# 1-Schematic_ISM_WAVER.net
KiCad netlist of a schematic drawn in EasyEDA
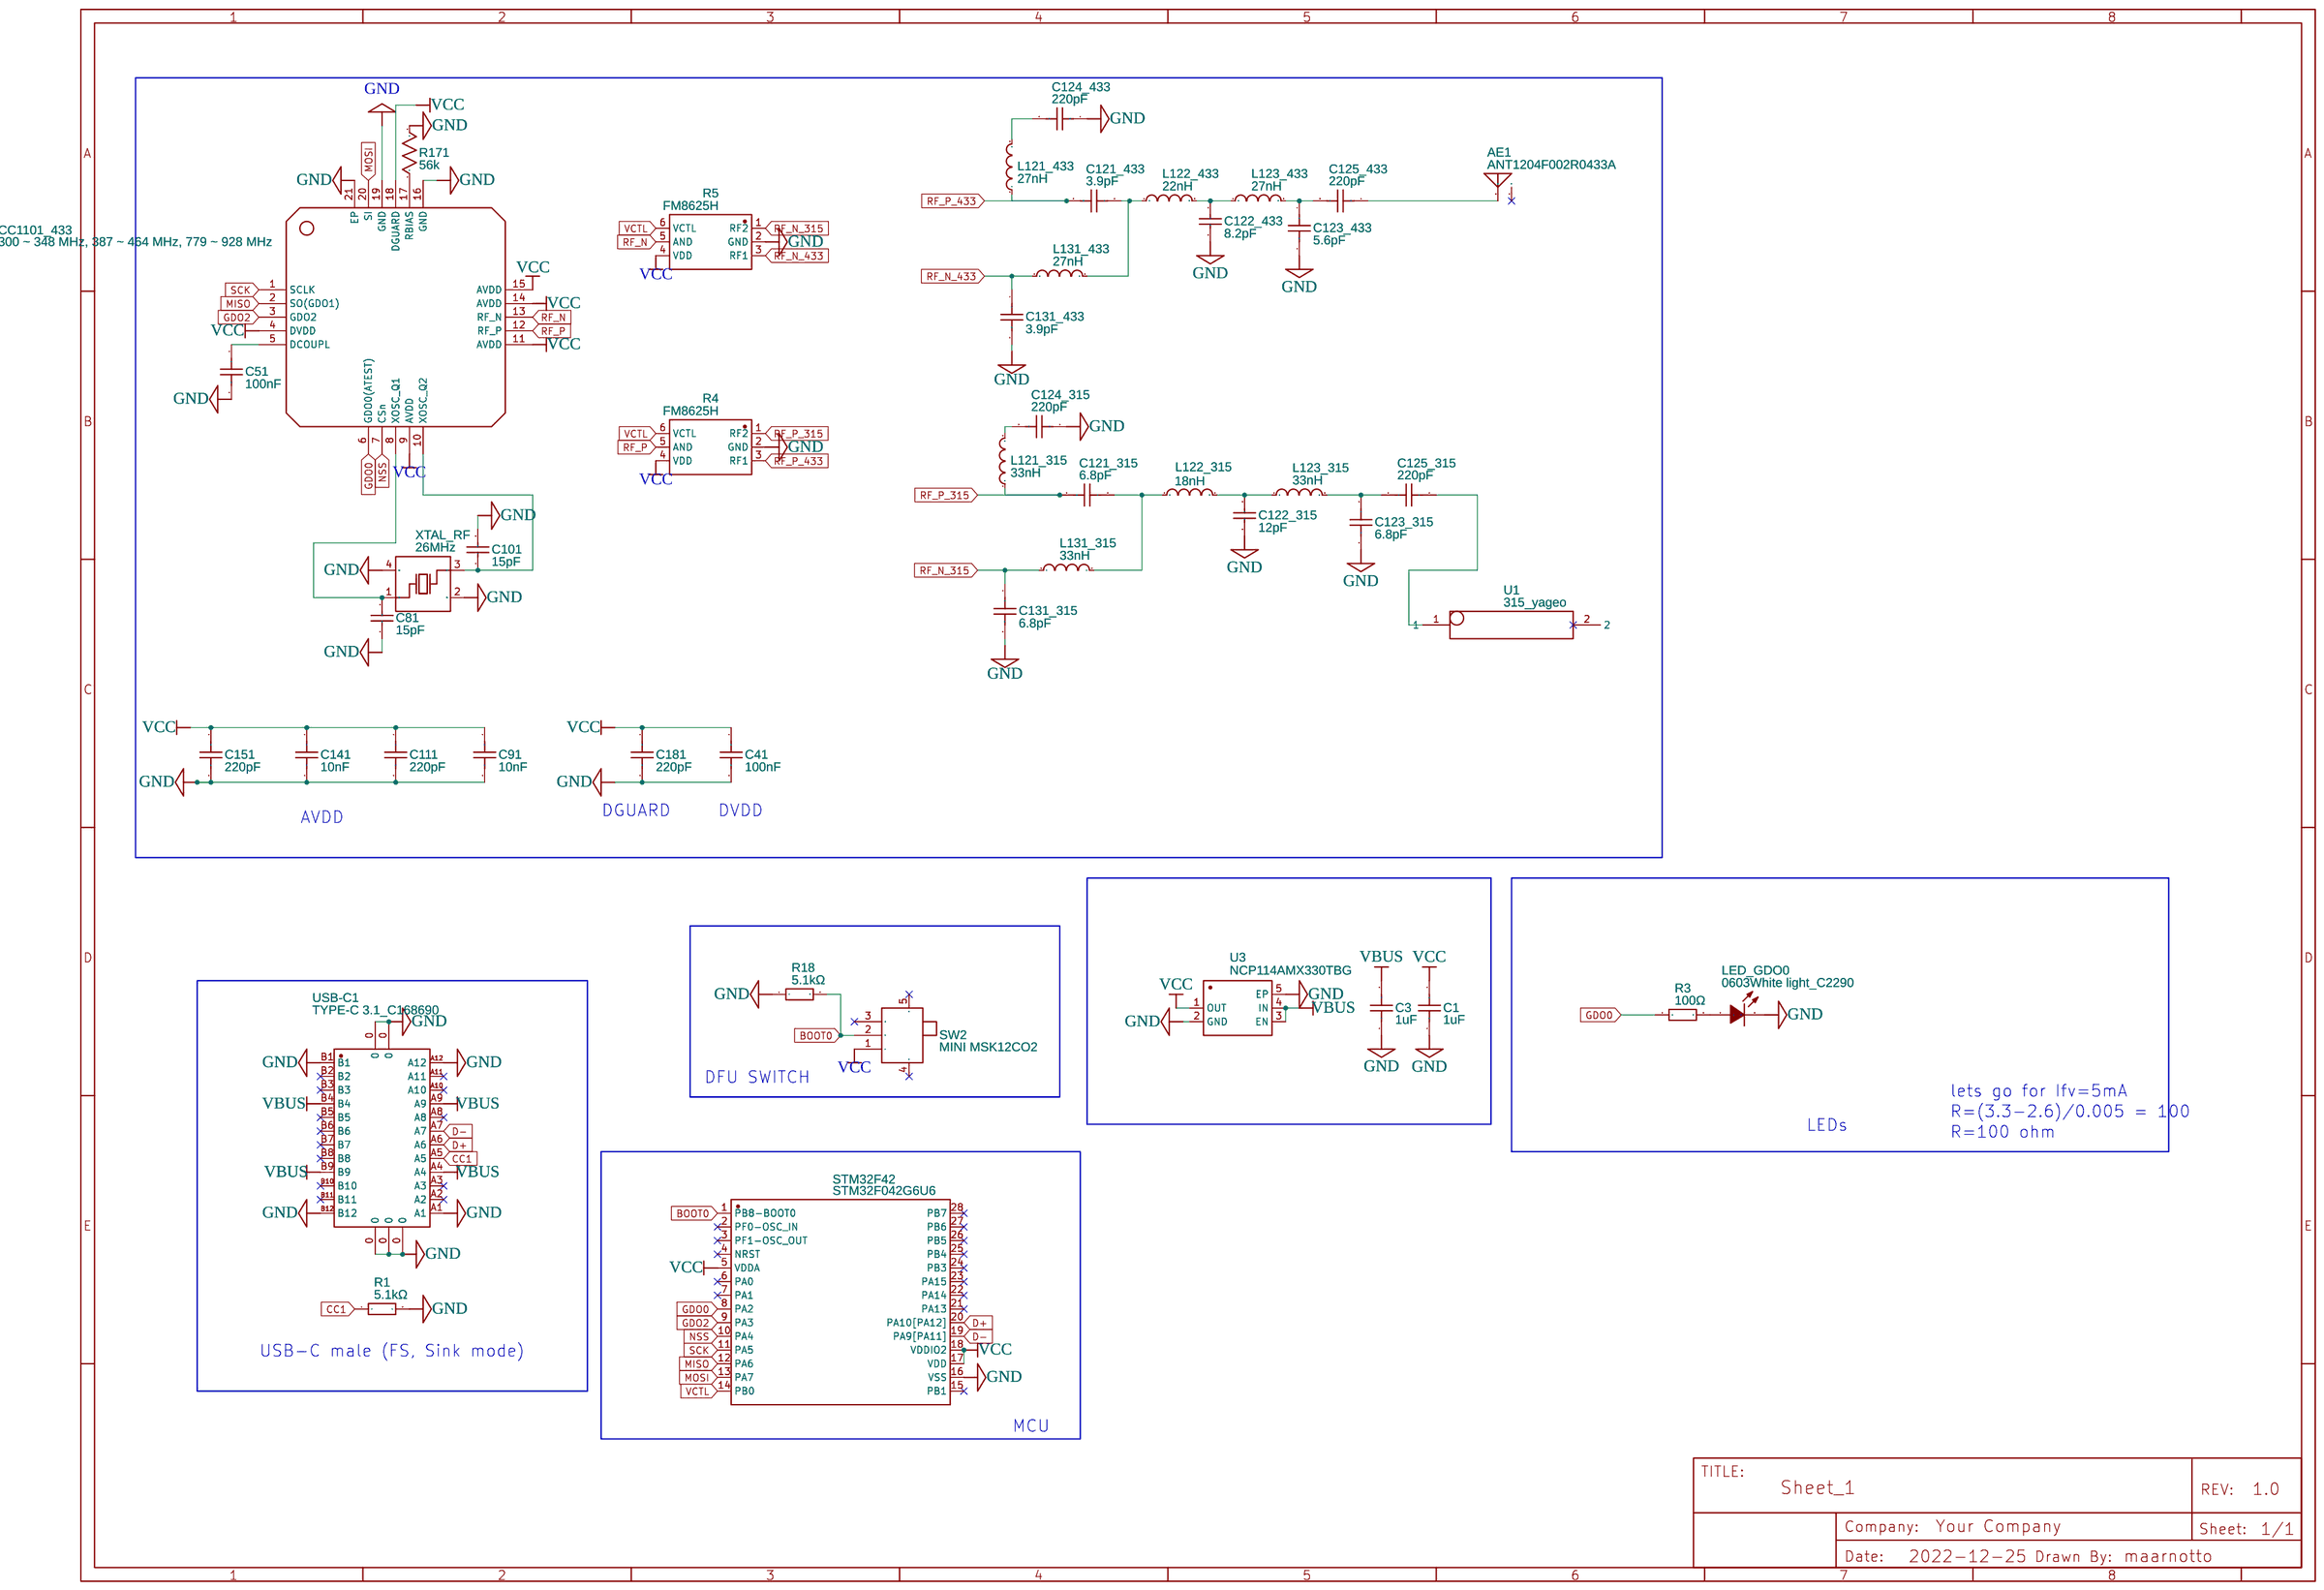
[diagram p0: schematic sheet]

(export (version "E")
  (design (tool "Eeschema 10.0.6"))
  (components
    (comp (ref "AE1")
      (value "ANT1204F002R0433A")
      (fields (field (name "Manufacturer") "YAGEO(国巨)"))
      (libsource (lib "") (part "ANT1204F002R0433A"))
    )
    (comp (ref "C1") (value "1uF") (libsource (lib "") (part "C_0603_US")))
    (comp (ref "C3") (value "1uF") (libsource (lib "") (part "C_0603_US")))
    (comp (ref "C41") (value "100nF") (libsource (lib "") (part "C_0402_US_1")))
    (comp (ref "C51") (value "100nF") (libsource (lib "") (part "C_0402_US_1")))
    (comp (ref "C81")
      (value "15pF")
      (fields (field (name "Manufacturer Part") "0402CG150J500NT") (field (name "Manufacturer") "FH(风华)"))
      (libsource (lib "") (part "0402CG150J500NT"))
    )
    (comp (ref "C91") (value "10nF") (libsource (lib "") (part "C_0402_US_1")))
    (comp (ref "C101")
      (value "15pF")
      (fields (field (name "Manufacturer Part") "0402CG150J500NT") (field (name "Manufacturer") "FH(风华)"))
      (libsource (lib "") (part "0402CG150J500NT"))
    )
    (comp (ref "C111") (value "220pF") (libsource (lib "") (part "C_0402_US_1")))
    (comp (ref "C121_315") (value "6.8pF") (libsource (lib "") (part "C_0402_US_2")))
    (comp (ref "C121_433") (value "3.9pF") (libsource (lib "") (part "C_0402_US_2")))
    (comp (ref "C122_315")
      (value "12pF")
      (fields (field (name "Manufacturer Part") "0402CG8R2C500NT") (field (name "Manufacturer") "FH(风华)"))
      (libsource (lib "") (part "0402CG8R2C500NT"))
    )
    (comp (ref "C122_433")
      (value "8.2pF")
      (fields (field (name "Manufacturer Part") "0402CG8R2C500NT") (field (name "Manufacturer") "FH(风华)"))
      (libsource (lib "") (part "0402CG8R2C500NT"))
    )
    (comp (ref "C123_315") (value "6.8pF") (libsource (lib "") (part "C_0402_US_3")))
    (comp (ref "C123_433") (value "5.6pF") (libsource (lib "") (part "C_0402_US_3")))
    (comp (ref "C124_315") (value "220pF") (libsource (lib "") (part "C_0402_US")))
    (comp (ref "C124_433") (value "220pF") (libsource (lib "") (part "C_0402_US")))
    (comp (ref "C125_315") (value "220pF") (libsource (lib "") (part "C_0402_US_4")))
    (comp (ref "C125_433") (value "220pF") (libsource (lib "") (part "C_0402_US_4")))
    (comp (ref "C131_315") (value "6.8pF") (libsource (lib "") (part "C_0402_US_5")))
    (comp (ref "C131_433") (value "3.9pF") (libsource (lib "") (part "C_0402_US_5")))
    (comp (ref "C141") (value "10nF") (libsource (lib "") (part "C_0402_US_1")))
    (comp (ref "C151") (value "220pF") (libsource (lib "") (part "C_0402_US_1")))
    (comp (ref "C181") (value "220pF") (libsource (lib "") (part "C_0402_US_1")))
    (comp (ref "CC1101_433")
      (value "300 ~ 348 MHz, 387 ~ 464 MHz, 779 ~ 928 MHz")
      (fields (field (name "Manufacturer Part") "CC1101RGPR") (field (name "Manufacturer") "TI(德州仪器)"))
      (libsource (lib "") (part "CC1101RGPR"))
    )
    (comp (ref "L121_315") (value "33nH") (libsource (lib "") (part "L0402_US")))
    (comp (ref "L121_433") (value "27nH") (libsource (lib "") (part "L0402_US")))
    (comp (ref "L122_315") (value "18nH") (libsource (lib "") (part "L0402_US_3")))
    (comp (ref "L122_433") (value "22nH") (libsource (lib "") (part "L0402_US_3")))
    (comp (ref "L123_315") (value "33nH") (libsource (lib "") (part "L0402_US_1")))
    (comp (ref "L123_433") (value "27nH") (libsource (lib "") (part "L0402_US_1")))
    (comp (ref "L131_315") (value "33nH") (libsource (lib "") (part "L0402_US_2")))
    (comp (ref "L131_433") (value "27nH") (libsource (lib "") (part "L0402_US_2")))
    (comp (ref "LED_GDO0")
      (value "0603White light_C2290")
      (fields (field (name "Manufacturer Part") "KT-0603白灯") (field (name "Manufacturer") "KENTO"))
      (libsource (lib "") (part "0603White light_C2290"))
    )
    (comp (ref "R1")
      (value "5.1kΩ")
      (fields
        (field (name "Manufacturer Part") "0402WGF5101TCE")
        (field (name "Manufacturer") "UNI-ROYAL(厚声)")
      )
      (libsource (lib "") (part "0402WGF5101TCE"))
    )
    (comp (ref "R3")
      (value "100Ω")
      (fields
        (field (name "Manufacturer Part") "0603WAF1000T5E")
        (field (name "Manufacturer") "UNI-ROYAL(厚声)")
      )
      (libsource (lib "") (part "0603WAF1000T5E"))
    )
    (comp (ref "R4")
      (value "FM8625H")
      (fields (field (name "Manufacturer") "FM(富满)"))
      (libsource (lib "") (part "FM8625H"))
    )
    (comp (ref "R5")
      (value "FM8625H")
      (fields (field (name "Manufacturer") "FM(富满)"))
      (libsource (lib "") (part "FM8625H"))
    )
    (comp (ref "R18")
      (value "5.1kΩ")
      (fields
        (field (name "Manufacturer Part") "0402WGF5101TCE")
        (field (name "Manufacturer") "UNI-ROYAL(厚声)")
      )
      (libsource (lib "") (part "0402WGF5101TCE"))
    )
    (comp (ref "R171") (value "56k") (libsource (lib "") (part "R_0402_US")))
    (comp (ref "STM32F42")
      (value "STM32F042G6U6")
      (fields (field (name "Manufacturer") "ST(意法半导体)"))
      (libsource (lib "") (part "STM32F042G6U6"))
    )
    (comp (ref "SW2")
      (value "MINI MSK12CO2")
      (fields (field (name "Manufacturer") "SHOU HAN(首韩)"))
      (libsource (lib "") (part "MINI MSK12CO2"))
    )
    (comp (ref "U1")
      (value "315_yageo")
      (fields
        (field (name "Manufacturer Part") "ANT1204F002R0315A")
        (field (name "Manufacturer") "PULSE ELECTRONICS")
      )
      (libsource (lib "") (part "315_yageo"))
    )
    (comp (ref "U3")
      (value "NCP114AMX330TBG")
      (fields (field (name "Manufacturer") "onsemi(安森美)"))
      (libsource (lib "") (part "NCP114AMX330TBG"))
    )
    (comp (ref "USB-C1")
      (value "TYPE-C 3.1_C168690")
      (fields (field (name "Manufacturer Part") "918-118A2021Y40000") (field (name "Manufacturer") "精拓金"))
      (libsource (lib "") (part "TYPE-C 3.1_C168690"))
    )
    (comp (ref "XTAL_RF")
      (value "26MHz")
      (fields (field (name "Manufacturer Part") "TAXM26M4RDBCCT2T") (field (name "Manufacturer") "YJX(雅晶鑫)"))
      (libsource (lib "") (part "SMD-3225_4P26MHZ10PF10PPM-40&#126;+85℃"))
    )
  )
  (nets
    (net (code "1") (name "BOOT0") (class "Default")
      (node (ref "R18") (pin "2") (pinfunction "2_2") (pintype "input"))
      (node (ref "STM32F42") (pin "1") (pinfunction "PB8-BOOT0_1") (pintype "unspecified"))
      (node (ref "SW2") (pin "2") (pinfunction "2_2") (pintype "unspecified"))
    )
    (net (code "2") (name "CC1") (class "Default")
      (node (ref "R1") (pin "1") (pinfunction "1_1") (pintype "input"))
      (node (ref "USB-C1") (pin "A5") (pinfunction "A5_A5") (pintype "unspecified"))
    )
    (net (code "3") (name "D+") (class "Default")
      (node (ref "STM32F42") (pin "20") (pinfunction "PA10[PA12]_20") (pintype "unspecified"))
      (node (ref "USB-C1") (pin "A6") (pinfunction "A6_A6") (pintype "unspecified"))
    )
    (net (code "4") (name "D-") (class "Default")
      (node (ref "STM32F42") (pin "19") (pinfunction "PA9[PA11]_19") (pintype "unspecified"))
      (node (ref "USB-C1") (pin "A7") (pinfunction "A7_A7") (pintype "unspecified"))
    )
    (net (code "5") (name "GDO0") (class "Default")
      (node (ref "CC1101_433") (pin "6") (pinfunction "GDO0(ATEST)_6") (pintype "unspecified"))
      (node (ref "R3") (pin "1") (pinfunction "1_1") (pintype "input"))
      (node (ref "STM32F42") (pin "8") (pinfunction "PA2_8") (pintype "unspecified"))
    )
    (net (code "6") (name "GDO2") (class "Default")
      (node (ref "CC1101_433") (pin "3") (pinfunction "GDO2_3") (pintype "unspecified"))
      (node (ref "STM32F42") (pin "9") (pinfunction "PA3_9") (pintype "unspecified"))
    )
    (net (code "7") (name "GND") (class "Default")
      (node (ref "C1") (pin "1") (pinfunction "1_1") (pintype "unspecified"))
      (node (ref "C101") (pin "2") (pinfunction "2_2") (pintype "input"))
      (node (ref "C111") (pin "2") (pinfunction "2_2") (pintype "unspecified"))
      (node (ref "C122_315") (pin "1") (pinfunction "1_1") (pintype "input"))
      (node (ref "C122_433") (pin "1") (pinfunction "1_1") (pintype "input"))
      (node (ref "C123_315") (pin "2") (pinfunction "2_2") (pintype "unspecified"))
      (node (ref "C123_433") (pin "2") (pinfunction "2_2") (pintype "unspecified"))
      (node (ref "C124_315") (pin "1") (pinfunction "1_1") (pintype "unspecified"))
      (node (ref "C124_433") (pin "1") (pinfunction "1_1") (pintype "unspecified"))
      (node (ref "C131_315") (pin "2") (pinfunction "2_2") (pintype "unspecified"))
      (node (ref "C131_433") (pin "2") (pinfunction "2_2") (pintype "unspecified"))
      (node (ref "C141") (pin "2") (pinfunction "2_2") (pintype "unspecified"))
      (node (ref "C151") (pin "2") (pinfunction "2_2") (pintype "unspecified"))
      (node (ref "C181") (pin "2") (pinfunction "2_2") (pintype "unspecified"))
      (node (ref "C3") (pin "1") (pinfunction "1_1") (pintype "unspecified"))
      (node (ref "C41") (pin "2") (pinfunction "2_2") (pintype "unspecified"))
      (node (ref "C51") (pin "2") (pinfunction "2_2") (pintype "unspecified"))
      (node (ref "C81") (pin "1") (pinfunction "1_1") (pintype "input"))
      (node (ref "C91") (pin "2") (pinfunction "2_2") (pintype "unspecified"))
      (node (ref "CC1101_433") (pin "16") (pinfunction "GND_16") (pintype "unspecified"))
      (node (ref "CC1101_433") (pin "19") (pinfunction "GND_19") (pintype "unspecified"))
      (node (ref "CC1101_433") (pin "21") (pinfunction "EP_21") (pintype "unspecified"))
      (node (ref "LED_GDO0") (pin "2") (pinfunction "K_2") (pintype "unspecified"))
      (node (ref "R1") (pin "2") (pinfunction "2_2") (pintype "input"))
      (node (ref "R171") (pin "2") (pinfunction "2_2") (pintype "unspecified"))
      (node (ref "R18") (pin "1") (pinfunction "1_1") (pintype "input"))
      (node (ref "R4") (pin "2") (pinfunction "GND_2") (pintype "unspecified"))
      (node (ref "R5") (pin "2") (pinfunction "GND_2") (pintype "unspecified"))
      (node (ref "STM32F42") (pin "16") (pinfunction "VSS_16") (pintype "unspecified"))
      (node (ref "U3") (pin "2") (pinfunction "GND_2") (pintype "unspecified"))
      (node (ref "U3") (pin "5") (pinfunction "EP_5") (pintype "unspecified"))
      (node (ref "USB-C1") (pin "0") (pinfunction "0_0") (pintype "unspecified"))
      (node (ref "USB-C1") (pin "A1") (pinfunction "A1_A1") (pintype "unspecified"))
      (node (ref "USB-C1") (pin "A12") (pinfunction "A12_A12") (pintype "unspecified"))
      (node (ref "USB-C1") (pin "B1") (pinfunction "B1_B1") (pintype "unspecified"))
      (node (ref "USB-C1") (pin "B12") (pinfunction "B12_B12") (pintype "unspecified"))
      (node (ref "XTAL_RF") (pin "2") (pinfunction "GND_2") (pintype "unspecified"))
      (node (ref "XTAL_RF") (pin "4") (pinfunction "GND_4") (pintype "unspecified"))
    )
    (net (code "8") (name "MISO") (class "Default")
      (node (ref "CC1101_433") (pin "2") (pinfunction "SO(GDO1)_2") (pintype "unspecified"))
      (node (ref "STM32F42") (pin "12") (pinfunction "PA6_12") (pintype "unspecified"))
    )
    (net (code "9") (name "MOSI") (class "Default")
      (node (ref "CC1101_433") (pin "20") (pinfunction "SI_20") (pintype "unspecified"))
      (node (ref "STM32F42") (pin "13") (pinfunction "PA7_13") (pintype "unspecified"))
    )
    (net (code "10") (name "NSS") (class "Default")
      (node (ref "CC1101_433") (pin "7") (pinfunction "CSn_7") (pintype "unspecified"))
      (node (ref "STM32F42") (pin "10") (pinfunction "PA4_10") (pintype "unspecified"))
    )
    (net (code "11") (name "Net-(AE1-PadS1)") (class "Default")
      (node (ref "AE1") (pin "S1") (pinfunction "S1_S1") (pintype "unspecified"))
      (node (ref "C125_433") (pin "1") (pinfunction "1_1") (pintype "unspecified"))
    )
    (net (code "12") (name "Net-(C121_315-Pad1)") (class "Default")
      (node (ref "C121_315") (pin "1") (pinfunction "1_1") (pintype "unspecified"))
      (node (ref "L122_315") (pin "1") (pinfunction "1_1") (pintype "unspecified"))
      (node (ref "L131_315") (pin "2") (pinfunction "2_2") (pintype "unspecified"))
    )
    (net (code "13") (name "Net-(C121_433-Pad1)") (class "Default")
      (node (ref "C121_433") (pin "1") (pinfunction "1_1") (pintype "unspecified"))
      (node (ref "L122_433") (pin "1") (pinfunction "1_1") (pintype "unspecified"))
      (node (ref "L131_433") (pin "2") (pinfunction "2_2") (pintype "unspecified"))
    )
    (net (code "14") (name "Net-(C122_315-Pad2)") (class "Default")
      (node (ref "C122_315") (pin "2") (pinfunction "2_2") (pintype "input"))
      (node (ref "L122_315") (pin "2") (pinfunction "2_2") (pintype "unspecified"))
      (node (ref "L123_315") (pin "1") (pinfunction "1_1") (pintype "unspecified"))
    )
    (net (code "15") (name "Net-(C122_433-Pad2)") (class "Default")
      (node (ref "C122_433") (pin "2") (pinfunction "2_2") (pintype "input"))
      (node (ref "L122_433") (pin "2") (pinfunction "2_2") (pintype "unspecified"))
      (node (ref "L123_433") (pin "1") (pinfunction "1_1") (pintype "unspecified"))
    )
    (net (code "16") (name "Net-(C123_315-Pad1)") (class "Default")
      (node (ref "C123_315") (pin "1") (pinfunction "1_1") (pintype "unspecified"))
      (node (ref "C125_315") (pin "2") (pinfunction "2_2") (pintype "unspecified"))
      (node (ref "L123_315") (pin "2") (pinfunction "2_2") (pintype "unspecified"))
    )
    (net (code "17") (name "Net-(C123_433-Pad1)") (class "Default")
      (node (ref "C123_433") (pin "1") (pinfunction "1_1") (pintype "unspecified"))
      (node (ref "C125_433") (pin "2") (pinfunction "2_2") (pintype "unspecified"))
      (node (ref "L123_433") (pin "2") (pinfunction "2_2") (pintype "unspecified"))
    )
    (net (code "18") (name "Net-(C124_315-Pad2)") (class "Default")
      (node (ref "C124_315") (pin "2") (pinfunction "2_2") (pintype "unspecified"))
      (node (ref "L121_315") (pin "2") (pinfunction "2_2") (pintype "unspecified"))
    )
    (net (code "19") (name "Net-(C124_433-Pad2)") (class "Default")
      (node (ref "C124_433") (pin "2") (pinfunction "2_2") (pintype "unspecified"))
      (node (ref "L121_433") (pin "2") (pinfunction "2_2") (pintype "unspecified"))
    )
    (net (code "20") (name "Net-(C125_315-Pad1)") (class "Default")
      (node (ref "C125_315") (pin "1") (pinfunction "1_1") (pintype "unspecified"))
      (node (ref "U1") (pin "1") (pinfunction "1_1") (pintype "unspecified"))
    )
    (net (code "21") (name "Net-(CC1101_433-DCOUPL)") (class "Default")
      (node (ref "C51") (pin "1") (pinfunction "1_1") (pintype "unspecified"))
      (node (ref "CC1101_433") (pin "5") (pinfunction "DCOUPL_5") (pintype "unspecified"))
    )
    (net (code "22") (name "Net-(CC1101_433-RBIAS)") (class "Default")
      (node (ref "CC1101_433") (pin "17") (pinfunction "RBIAS_17") (pintype "unspecified"))
      (node (ref "R171") (pin "1") (pinfunction "1_1") (pintype "unspecified"))
    )
    (net (code "23") (name "Net-(CC1101_433-XOSC_Q1)") (class "Default")
      (node (ref "C81") (pin "2") (pinfunction "2_2") (pintype "input"))
      (node (ref "CC1101_433") (pin "8") (pinfunction "XOSC_Q1_8") (pintype "unspecified"))
      (node (ref "XTAL_RF") (pin "1") (pinfunction "OSC1_1") (pintype "unspecified"))
    )
    (net (code "24") (name "Net-(CC1101_433-XOSC_Q2)") (class "Default")
      (node (ref "C101") (pin "1") (pinfunction "1_1") (pintype "input"))
      (node (ref "CC1101_433") (pin "10") (pinfunction "XOSC_Q2_10") (pintype "unspecified"))
      (node (ref "XTAL_RF") (pin "3") (pinfunction "OSC2_3") (pintype "unspecified"))
    )
    (net (code "25") (name "Net-(LED_GDO0-A)") (class "Default")
      (node (ref "LED_GDO0") (pin "1") (pinfunction "A_1") (pintype "unspecified"))
      (node (ref "R3") (pin "2") (pinfunction "2_2") (pintype "input"))
    )
    (net (code "26") (name "RF_N") (class "Default")
      (node (ref "CC1101_433") (pin "13") (pinfunction "RF_N_13") (pintype "unspecified"))
      (node (ref "R5") (pin "5") (pinfunction "AND_5") (pintype "unspecified"))
    )
    (net (code "27") (name "RF_N_315") (class "Default")
      (node (ref "C131_315") (pin "1") (pinfunction "1_1") (pintype "unspecified"))
      (node (ref "L131_315") (pin "1") (pinfunction "1_1") (pintype "unspecified"))
      (node (ref "R5") (pin "1") (pinfunction "RF2_1") (pintype "unspecified"))
    )
    (net (code "28") (name "RF_N_433") (class "Default")
      (node (ref "C131_433") (pin "1") (pinfunction "1_1") (pintype "unspecified"))
      (node (ref "L131_433") (pin "1") (pinfunction "1_1") (pintype "unspecified"))
      (node (ref "R5") (pin "3") (pinfunction "RF1_3") (pintype "unspecified"))
    )
    (net (code "29") (name "RF_P") (class "Default")
      (node (ref "CC1101_433") (pin "12") (pinfunction "RF_P_12") (pintype "unspecified"))
      (node (ref "R4") (pin "5") (pinfunction "AND_5") (pintype "unspecified"))
    )
    (net (code "30") (name "RF_P_315") (class "Default")
      (node (ref "C121_315") (pin "2") (pinfunction "2_2") (pintype "unspecified"))
      (node (ref "L121_315") (pin "1") (pinfunction "1_1") (pintype "unspecified"))
      (node (ref "R4") (pin "1") (pinfunction "RF2_1") (pintype "unspecified"))
    )
    (net (code "31") (name "RF_P_433") (class "Default")
      (node (ref "C121_433") (pin "2") (pinfunction "2_2") (pintype "unspecified"))
      (node (ref "L121_433") (pin "1") (pinfunction "1_1") (pintype "unspecified"))
      (node (ref "R4") (pin "3") (pinfunction "RF1_3") (pintype "unspecified"))
    )
    (net (code "32") (name "SCK") (class "Default")
      (node (ref "CC1101_433") (pin "1") (pinfunction "SCLK_1") (pintype "unspecified"))
      (node (ref "STM32F42") (pin "11") (pinfunction "PA5_11") (pintype "unspecified"))
    )
    (net (code "33") (name "VBUS") (class "Default")
      (node (ref "C3") (pin "2") (pinfunction "2_2") (pintype "unspecified"))
      (node (ref "U3") (pin "3") (pinfunction "EN_3") (pintype "unspecified"))
      (node (ref "U3") (pin "4") (pinfunction "IN_4") (pintype "unspecified"))
      (node (ref "USB-C1") (pin "A4") (pinfunction "A4_A4") (pintype "unspecified"))
      (node (ref "USB-C1") (pin "A9") (pinfunction "A9_A9") (pintype "unspecified"))
      (node (ref "USB-C1") (pin "B4") (pinfunction "B4_B4") (pintype "unspecified"))
      (node (ref "USB-C1") (pin "B9") (pinfunction "B9_B9") (pintype "unspecified"))
    )
    (net (code "34") (name "VCC") (class "Default")
      (node (ref "C1") (pin "2") (pinfunction "2_2") (pintype "unspecified"))
      (node (ref "C111") (pin "1") (pinfunction "1_1") (pintype "unspecified"))
      (node (ref "C141") (pin "1") (pinfunction "1_1") (pintype "unspecified"))
      (node (ref "C151") (pin "1") (pinfunction "1_1") (pintype "unspecified"))
      (node (ref "C181") (pin "1") (pinfunction "1_1") (pintype "unspecified"))
      (node (ref "C41") (pin "1") (pinfunction "1_1") (pintype "unspecified"))
      (node (ref "C91") (pin "1") (pinfunction "1_1") (pintype "unspecified"))
      (node (ref "CC1101_433") (pin "11") (pinfunction "AVDD_11") (pintype "unspecified"))
      (node (ref "CC1101_433") (pin "14") (pinfunction "AVDD_14") (pintype "unspecified"))
      (node (ref "CC1101_433") (pin "15") (pinfunction "AVDD_15") (pintype "unspecified"))
      (node (ref "CC1101_433") (pin "18") (pinfunction "DGUARD_18") (pintype "unspecified"))
      (node (ref "CC1101_433") (pin "4") (pinfunction "DVDD_4") (pintype "unspecified"))
      (node (ref "CC1101_433") (pin "9") (pinfunction "AVDD_9") (pintype "unspecified"))
      (node (ref "R4") (pin "4") (pinfunction "VDD_4") (pintype "unspecified"))
      (node (ref "R5") (pin "4") (pinfunction "VDD_4") (pintype "unspecified"))
      (node (ref "STM32F42") (pin "17") (pinfunction "VDD_17") (pintype "unspecified"))
      (node (ref "STM32F42") (pin "18") (pinfunction "VDDIO2_18") (pintype "unspecified"))
      (node (ref "STM32F42") (pin "5") (pinfunction "VDDA_5") (pintype "unspecified"))
      (node (ref "SW2") (pin "1") (pinfunction "1_1") (pintype "unspecified"))
      (node (ref "U3") (pin "1") (pinfunction "OUT_1") (pintype "unspecified"))
    )
    (net (code "35") (name "VCTL") (class "Default")
      (node (ref "R4") (pin "6") (pinfunction "VCTL_6") (pintype "unspecified"))
      (node (ref "R5") (pin "6") (pinfunction "VCTL_6") (pintype "unspecified"))
      (node (ref "STM32F42") (pin "14") (pinfunction "PB0_14") (pintype "unspecified"))
    )
    (net (code "36") (name "unconnected-(AE1-PadS2)") (class "Default")
      (node (ref "AE1") (pin "S2") (pinfunction "S2_S2") (pintype "unspecified+no_connect"))
    )
    (net (code "37") (name "unconnected-(STM32F42-NRST-Pad4)") (class "Default")
      (node (ref "STM32F42") (pin "4") (pinfunction "NRST_4") (pintype "unspecified+no_connect"))
    )
    (net (code "38") (name "unconnected-(STM32F42-PA0-Pad6)") (class "Default")
      (node (ref "STM32F42") (pin "6") (pinfunction "PA0_6") (pintype "unspecified+no_connect"))
    )
    (net (code "39") (name "unconnected-(STM32F42-PA1-Pad7)") (class "Default")
      (node (ref "STM32F42") (pin "7") (pinfunction "PA1_7") (pintype "unspecified+no_connect"))
    )
    (net (code "40") (name "unconnected-(STM32F42-PA13-Pad21)") (class "Default")
      (node (ref "STM32F42") (pin "21") (pinfunction "PA13_21") (pintype "unspecified+no_connect"))
    )
    (net (code "41") (name "unconnected-(STM32F42-PA14-Pad22)") (class "Default")
      (node (ref "STM32F42") (pin "22") (pinfunction "PA14_22") (pintype "unspecified+no_connect"))
    )
    (net (code "42") (name "unconnected-(STM32F42-PA15-Pad23)") (class "Default")
      (node (ref "STM32F42") (pin "23") (pinfunction "PA15_23") (pintype "unspecified+no_connect"))
    )
    (net (code "43") (name "unconnected-(STM32F42-PB1-Pad15)") (class "Default")
      (node (ref "STM32F42") (pin "15") (pinfunction "PB1_15") (pintype "unspecified+no_connect"))
    )
    (net (code "44") (name "unconnected-(STM32F42-PB3-Pad24)") (class "Default")
      (node (ref "STM32F42") (pin "24") (pinfunction "PB3_24") (pintype "unspecified+no_connect"))
    )
    (net (code "45") (name "unconnected-(STM32F42-PB4-Pad25)") (class "Default")
      (node (ref "STM32F42") (pin "25") (pinfunction "PB4_25") (pintype "unspecified+no_connect"))
    )
    (net (code "46") (name "unconnected-(STM32F42-PB5-Pad26)") (class "Default")
      (node (ref "STM32F42") (pin "26") (pinfunction "PB5_26") (pintype "unspecified+no_connect"))
    )
    (net (code "47") (name "unconnected-(STM32F42-PB6-Pad27)") (class "Default")
      (node (ref "STM32F42") (pin "27") (pinfunction "PB6_27") (pintype "unspecified+no_connect"))
    )
    (net (code "48") (name "unconnected-(STM32F42-PB7-Pad28)") (class "Default")
      (node (ref "STM32F42") (pin "28") (pinfunction "PB7_28") (pintype "unspecified+no_connect"))
    )
    (net (code "49") (name "unconnected-(STM32F42-PF0-OSC_IN-Pad2)") (class "Default")
      (node (ref "STM32F42") (pin "2") (pinfunction "PF0-OSC_IN_2") (pintype "unspecified+no_connect"))
    )
    (net (code "50") (name "unconnected-(STM32F42-PF1-OSC_OUT-Pad3)") (class "Default")
      (node (ref "STM32F42") (pin "3") (pinfunction "PF1-OSC_OUT_3") (pintype "unspecified+no_connect"))
    )
    (net (code "51") (name "unconnected-(SW2-Pad3)") (class "Default")
      (node (ref "SW2") (pin "3") (pinfunction "3_3") (pintype "unspecified+no_connect"))
    )
    (net (code "52") (name "unconnected-(SW2-Pad4)") (class "Default")
      (node (ref "SW2") (pin "4") (pinfunction "4_4") (pintype "unspecified+no_connect"))
    )
    (net (code "53") (name "unconnected-(SW2-Pad5)") (class "Default")
      (node (ref "SW2") (pin "5") (pinfunction "5_5") (pintype "unspecified+no_connect"))
    )
    (net (code "54") (name "unconnected-(U1-Pad2)") (class "Default")
      (node (ref "U1") (pin "2") (pinfunction "2_2") (pintype "unspecified+no_connect"))
    )
    (net (code "55") (name "unconnected-(USB-C1-PadA2)") (class "Default")
      (node (ref "USB-C1") (pin "A2") (pinfunction "A2_A2") (pintype "unspecified+no_connect"))
    )
    (net (code "56") (name "unconnected-(USB-C1-PadA3)") (class "Default")
      (node (ref "USB-C1") (pin "A3") (pinfunction "A3_A3") (pintype "unspecified+no_connect"))
    )
    (net (code "57") (name "unconnected-(USB-C1-PadA8)") (class "Default")
      (node (ref "USB-C1") (pin "A8") (pinfunction "A8_A8") (pintype "unspecified+no_connect"))
    )
    (net (code "58") (name "unconnected-(USB-C1-PadA10)") (class "Default")
      (node (ref "USB-C1") (pin "A10") (pinfunction "A10_A10") (pintype "unspecified+no_connect"))
    )
    (net (code "59") (name "unconnected-(USB-C1-PadA11)") (class "Default")
      (node (ref "USB-C1") (pin "A11") (pinfunction "A11_A11") (pintype "unspecified+no_connect"))
    )
    (net (code "60") (name "unconnected-(USB-C1-PadB2)") (class "Default")
      (node (ref "USB-C1") (pin "B2") (pinfunction "B2_B2") (pintype "unspecified+no_connect"))
    )
    (net (code "61") (name "unconnected-(USB-C1-PadB3)") (class "Default")
      (node (ref "USB-C1") (pin "B3") (pinfunction "B3_B3") (pintype "unspecified+no_connect"))
    )
    (net (code "62") (name "unconnected-(USB-C1-PadB5)") (class "Default")
      (node (ref "USB-C1") (pin "B5") (pinfunction "B5_B5") (pintype "unspecified+no_connect"))
    )
    (net (code "63") (name "unconnected-(USB-C1-PadB6)") (class "Default")
      (node (ref "USB-C1") (pin "B6") (pinfunction "B6_B6") (pintype "unspecified+no_connect"))
    )
    (net (code "64") (name "unconnected-(USB-C1-PadB7)") (class "Default")
      (node (ref "USB-C1") (pin "B7") (pinfunction "B7_B7") (pintype "unspecified+no_connect"))
    )
    (net (code "65") (name "unconnected-(USB-C1-PadB8)") (class "Default")
      (node (ref "USB-C1") (pin "B8") (pinfunction "B8_B8") (pintype "unspecified+no_connect"))
    )
    (net (code "66") (name "unconnected-(USB-C1-PadB10)") (class "Default")
      (node (ref "USB-C1") (pin "B10") (pinfunction "B10_B10") (pintype "unspecified+no_connect"))
    )
    (net (code "67") (name "unconnected-(USB-C1-PadB11)") (class "Default")
      (node (ref "USB-C1") (pin "B11") (pinfunction "B11_B11") (pintype "unspecified+no_connect"))
    )
  )
)
